# MainBoard_V100_TEMP.net
KiCad netlist of a schematic drawn in Altium Designer
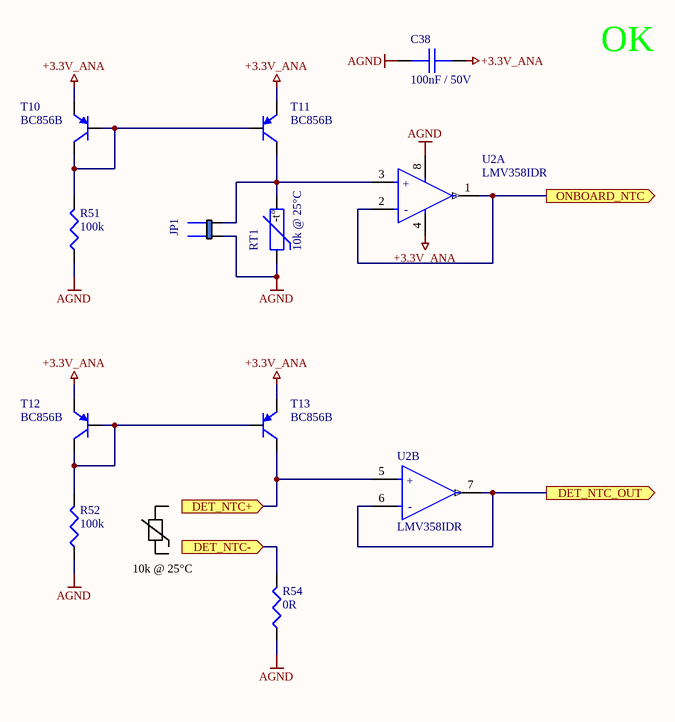
[diagram p0: MainBoard_V100_TEMP.SchDoc]

(export (version "E")
  (design (tool "Eeschema 10.0.6"))
  (components
    (comp (ref "C38")
      (value "100nF / 50V")
      (footprint "0805_C")
      (description "100nF 50V X7R")
      (fields (field (name "PART NUMBER") "SMD0805-100nF-50V"))
      (libsource (lib "ALTIUM_DB_LIB") (part "CAP_NONPOL"))
    )
    (comp (ref "JP1")
      (value "JUMPER2 2.54MM")
      (footprint "JUMPER_5")
      (libsource (lib "ALTIUM_DB_LIB") (part "JUMPER2"))
    )
    (comp (ref "R51")
      (value "100k")
      (footprint "0805")
      (description "100k 0805 0.125W 5%")
      (fields (field (name "PART NUMBER") "SMD0805-100k 5%"))
      (libsource (lib "ALTIUM_DB_LIB") (part "RESISTOR"))
    )
    (comp (ref "R52")
      (value "100k")
      (footprint "0805")
      (description "100k 0805 0.125W 5%")
      (fields (field (name "PART NUMBER") "SMD0805-100k 5%"))
      (libsource (lib "ALTIUM_DB_LIB") (part "RESISTOR"))
    )
    (comp (ref "R54")
      (value "0R")
      (footprint "0805")
      (description "0R 0805 0.125W 5%")
      (fields (field (name "PART NUMBER") "0 R 5%"))
      (libsource (lib "ALTIUM_DB_LIB") (part "RESISTOR"))
    )
    (comp (ref "RT1")
      (value "10k @ 25°C")
      (footprint "0805")
      (description "NTC (Negative Temperature Coefficient) Thermistors THERMISTOR 0805 10K/3435")
      (fields (field (name "PART NUMBER") "TX08F103F3435ER"))
      (libsource (lib "ALTIUM_DB_LIB") (part "NTC_GENERAL"))
    )
    (comp (ref "T10")
      (value "BC856B")
      (footprint "SOT-23")
      (description "BC856B Bipolar (BJT) Single Transistor, PNP, 65 V, 100 mA, 250 mW, SOT-23, Surface Mount")
      (libsource (lib "ALTIUM_DB_LIB") (part "BJT_PNP"))
    )
    (comp (ref "T11")
      (value "BC856B")
      (footprint "SOT-23")
      (description "BC856B Bipolar (BJT) Single Transistor, PNP, 65 V, 100 mA, 250 mW, SOT-23, Surface Mount")
      (libsource (lib "ALTIUM_DB_LIB") (part "BJT_PNP"))
    )
    (comp (ref "T12")
      (value "BC856B")
      (footprint "SOT-23")
      (description "BC856B Bipolar (BJT) Single Transistor, PNP, 65 V, 100 mA, 250 mW, SOT-23, Surface Mount")
      (libsource (lib "ALTIUM_DB_LIB") (part "BJT_PNP"))
    )
    (comp (ref "T13")
      (value "BC856B")
      (footprint "SOT-23")
      (description "BC856B Bipolar (BJT) Single Transistor, PNP, 65 V, 100 mA, 250 mW, SOT-23, Surface Mount")
      (libsource (lib "ALTIUM_DB_LIB") (part "BJT_PNP"))
    )
    (comp (ref "U2")
      (value "LMV358IDR")
      (footprint "SO-8")
      (description "IC OPAMP GP 2 CIRCUIT 8SOIC")
      (libsource (lib "ALTIUM_DB_LIB") (part "LMV358IDR"))
    )
  )
  (nets
    (net (code "1") (name "+3.3V_ANA") (class "Default")
      (node (ref "C38") (pin "2") (pintype "passive"))
      (node (ref "T10") (pin "2") (pinfunction "E_2") (pintype "passive"))
      (node (ref "T11") (pin "2") (pinfunction "E_2") (pintype "passive"))
      (node (ref "T12") (pin "2") (pinfunction "E_2") (pintype "passive"))
      (node (ref "T13") (pin "2") (pinfunction "E_2") (pintype "passive"))
      (node (ref "U2") (pin "4") (pinfunction "GND_4") (pintype "power_in"))
    )
    (net (code "2") (name "/DET_NTC+") (class "Default")
      (node (ref "T13") (pin "3") (pinfunction "C_3") (pintype "passive"))
      (node (ref "U2") (pin "5") (pinfunction "2IN+_5") (pintype "tri_state"))
    )
    (net (code "3") (name "/DET_NTC-") (class "Default") (node (ref "R54") (pin "2") (pintype "passive")))
    (net (code "4") (name "/DET_NTC_OUT") (class "Default")
      (node (ref "U2") (pin "6") (pinfunction "2IN-_6") (pintype "tri_state"))
      (node (ref "U2") (pin "7") (pinfunction "2OUT_7") (pintype "output"))
    )
    (net (code "5") (name "/ONBOARD_NTC") (class "Default")
      (node (ref "U2") (pin "1") (pinfunction "OUT_1") (pintype "output"))
      (node (ref "U2") (pin "2") (pinfunction "1IN-_2") (pintype "tri_state"))
    )
    (net (code "6") (name "AGND") (class "Default")
      (node (ref "C38") (pin "1") (pintype "passive"))
      (node (ref "JP1") (pin "1") (pinfunction "1_1") (pintype "passive"))
      (node (ref "R51") (pin "1") (pintype "passive"))
      (node (ref "R52") (pin "1") (pintype "passive"))
      (node (ref "R54") (pin "1") (pintype "passive"))
      (node (ref "RT1") (pin "1") (pintype "passive"))
      (node (ref "U2") (pin "8") (pinfunction "VCC+_8") (pintype "power_in"))
    )
    (net (code "7") (name "Net-(T10-B)") (class "Default")
      (node (ref "R51") (pin "2") (pintype "passive"))
      (node (ref "T10") (pin "1") (pinfunction "B_1") (pintype "passive"))
      (node (ref "T10") (pin "3") (pinfunction "C_3") (pintype "passive"))
      (node (ref "T11") (pin "1") (pinfunction "B_1") (pintype "passive"))
    )
    (net (code "8") (name "Net-(T11-C)") (class "Default")
      (node (ref "JP1") (pin "2") (pinfunction "2_2") (pintype "passive"))
      (node (ref "RT1") (pin "2") (pintype "passive"))
      (node (ref "T11") (pin "3") (pinfunction "C_3") (pintype "passive"))
      (node (ref "U2") (pin "3") (pinfunction "1IN+_3") (pintype "tri_state"))
    )
    (net (code "9") (name "Net-(T12-B)") (class "Default")
      (node (ref "R52") (pin "2") (pintype "passive"))
      (node (ref "T12") (pin "1") (pinfunction "B_1") (pintype "passive"))
      (node (ref "T12") (pin "3") (pinfunction "C_3") (pintype "passive"))
      (node (ref "T13") (pin "1") (pinfunction "B_1") (pintype "passive"))
    )
  )
)
